# pragotron-master-clock-1_0.net
KiCad netlist of a schematic drawn in EAGLE
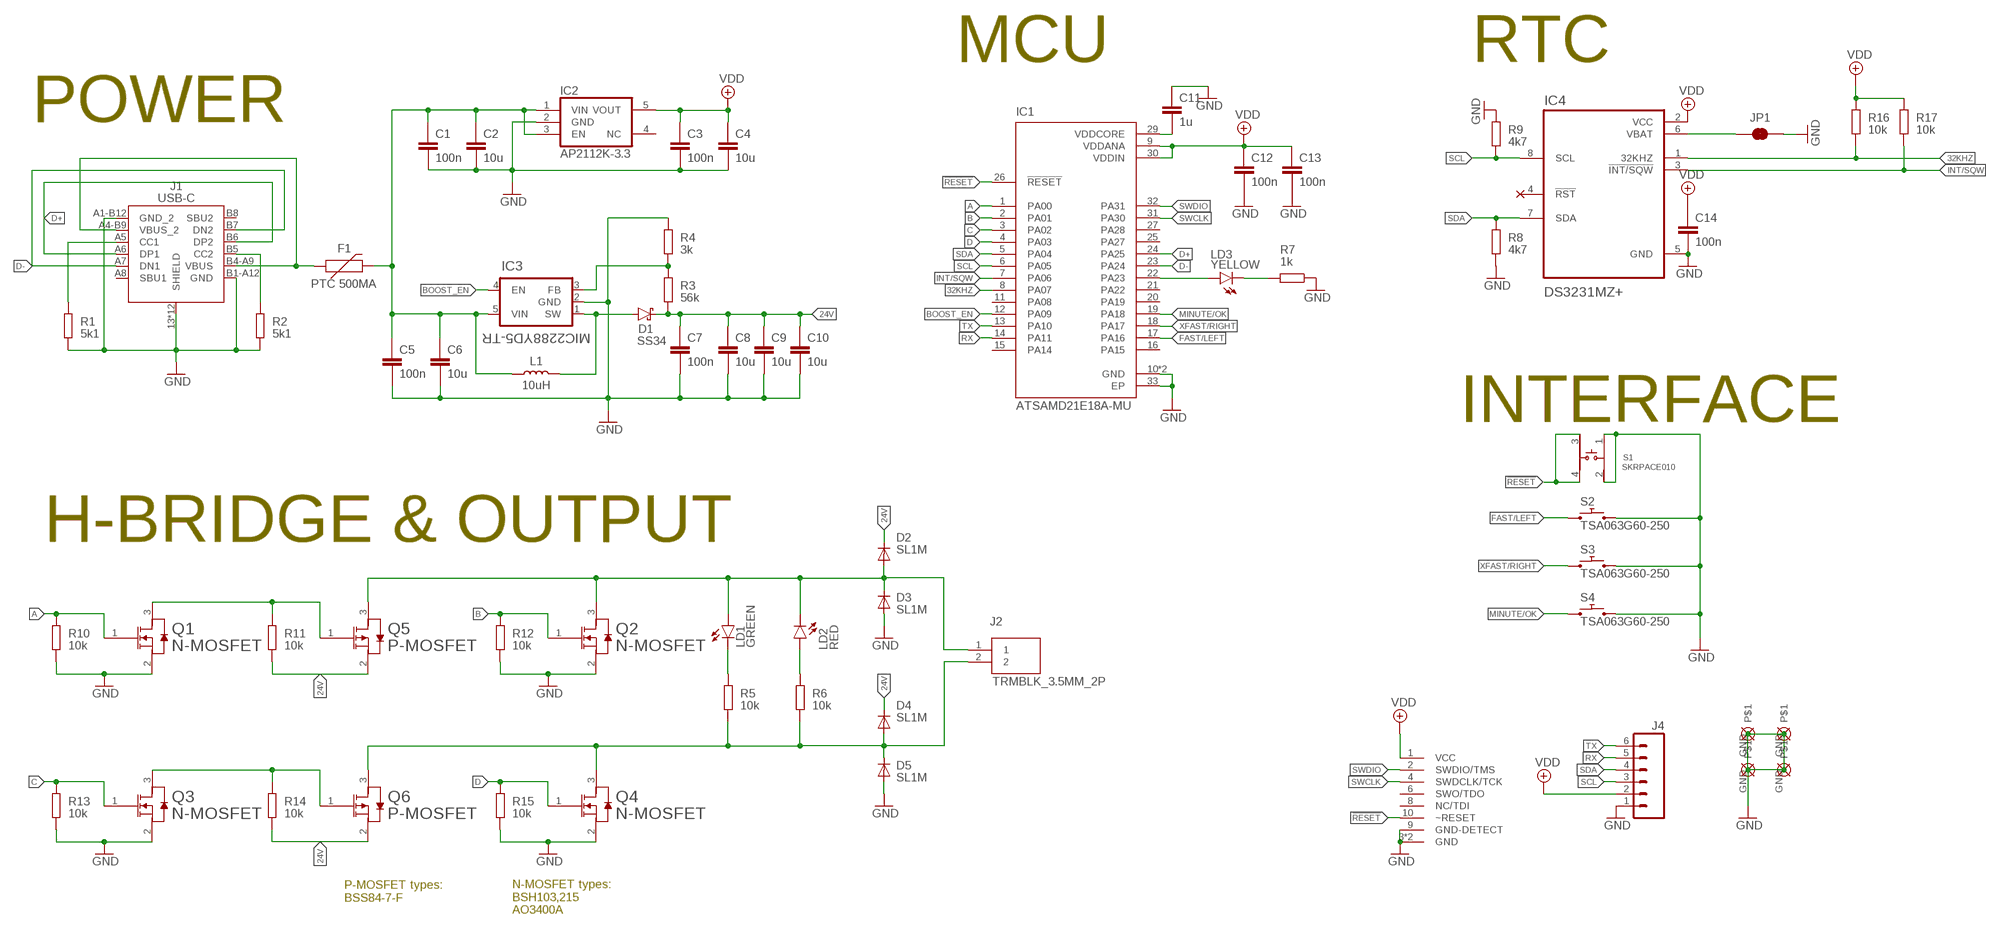
[diagram p0: schematic, sheet 1]

(export (version "E")
  (design (tool "Eeschema 10.0.6"))
  (components
    (comp (ref "C1")
      (value "100n")
      (footprint "eagle-import:CAPACITOR0603")
      (libsource (lib "eagle-import") (part "CAPACITOR0603"))
    )
    (comp (ref "C2")
      (value "10u")
      (footprint "eagle-import:CAPACITOR0805")
      (libsource (lib "eagle-import") (part "CAPACITOR0805"))
    )
    (comp (ref "C3")
      (value "100n")
      (footprint "eagle-import:CAPACITOR0603")
      (libsource (lib "eagle-import") (part "CAPACITOR0603"))
    )
    (comp (ref "C4")
      (value "10u")
      (footprint "eagle-import:CAPACITOR0805")
      (libsource (lib "eagle-import") (part "CAPACITOR0805"))
    )
    (comp (ref "C5")
      (value "100n")
      (footprint "eagle-import:CAPACITOR0603")
      (libsource (lib "eagle-import") (part "CAPACITOR0603"))
    )
    (comp (ref "C6")
      (value "10u")
      (footprint "eagle-import:CAPACITOR0805")
      (libsource (lib "eagle-import") (part "CAPACITOR0805"))
    )
    (comp (ref "C7")
      (value "100n")
      (footprint "eagle-import:CAPACITOR0603")
      (libsource (lib "eagle-import") (part "CAPACITOR0603"))
    )
    (comp (ref "C8")
      (value "10u")
      (footprint "eagle-import:CAPACITOR0805")
      (libsource (lib "eagle-import") (part "CAPACITOR0805"))
    )
    (comp (ref "C9")
      (value "10u")
      (footprint "eagle-import:CAPACITOR0805")
      (libsource (lib "eagle-import") (part "CAPACITOR0805"))
    )
    (comp (ref "C10")
      (value "10u")
      (footprint "eagle-import:CAPACITOR0805")
      (libsource (lib "eagle-import") (part "CAPACITOR0805"))
    )
    (comp (ref "C11")
      (value "1u")
      (footprint "eagle-import:CAPACITOR0603")
      (libsource (lib "eagle-import") (part "CAPACITOR0603"))
    )
    (comp (ref "C12")
      (value "100n")
      (footprint "eagle-import:CAPACITOR0603")
      (libsource (lib "eagle-import") (part "CAPACITOR0603"))
    )
    (comp (ref "C13")
      (value "100n")
      (footprint "eagle-import:CAPACITOR0603")
      (libsource (lib "eagle-import") (part "CAPACITOR0603"))
    )
    (comp (ref "C14")
      (value "100n")
      (footprint "eagle-import:CAPACITOR0603")
      (libsource (lib "eagle-import") (part "CAPACITOR0603"))
    )
    (comp (ref "D1")
      (value "SS34")
      (footprint "eagle-import:SMA")
      (libsource (lib "eagle-import") (part "SS34"))
    )
    (comp (ref "D2")
      (value "SL1M")
      (footprint "eagle-import:SOD123")
      (libsource (lib "eagle-import") (part "SL1M"))
    )
    (comp (ref "D3")
      (value "SL1M")
      (footprint "eagle-import:SOD123")
      (libsource (lib "eagle-import") (part "SL1M"))
    )
    (comp (ref "D4")
      (value "SL1M")
      (footprint "eagle-import:SOD123")
      (libsource (lib "eagle-import") (part "SL1M"))
    )
    (comp (ref "D5")
      (value "SL1M")
      (footprint "eagle-import:SOD123")
      (libsource (lib "eagle-import") (part "SL1M"))
    )
    (comp (ref "F1")
      (value "PTC 500MA")
      (footprint "eagle-import:PTC0805")
      (fields (field (name "MPN") "SR020-09"))
      (libsource (lib "eagle-import") (part "PTC200MA"))
    )
    (comp (ref "H1")
      (value "HOLE_3MM_GND_CORNER")
      (footprint "eagle-import:3MM_HOLE_GND_CORNER")
      (libsource (lib "eagle-import") (part "HOLE_3MM_GND_CORNER"))
    )
    (comp (ref "H2")
      (value "HOLE_3MM_GND_CORNER")
      (footprint "eagle-import:3MM_HOLE_GND_CORNER")
      (libsource (lib "eagle-import") (part "HOLE_3MM_GND_CORNER"))
    )
    (comp (ref "H3")
      (value "HOLE_3MM_GND_CORNER")
      (footprint "eagle-import:3MM_HOLE_GND_CORNER")
      (libsource (lib "eagle-import") (part "HOLE_3MM_GND_CORNER"))
    )
    (comp (ref "H4")
      (value "HOLE_3MM_GND_CORNER")
      (footprint "eagle-import:3MM_HOLE_GND_CORNER")
      (libsource (lib "eagle-import") (part "HOLE_3MM_GND_CORNER"))
    )
    (comp (ref "IC1")
      (value "ATSAMD21E18A-MU")
      (footprint "eagle-import:QFN50P500X500X100-33N")
      (fields (field (name "DIGIKEY_PART_NUMBER") "ATSAMD21E18A-MU-ND") (field (name "MF") "Microchip"))
      (libsource (lib "eagle-import") (part "ATSAMD21E18A-MU"))
    )
    (comp (ref "IC2")
      (value "AP2112K-3.3")
      (footprint "eagle-import:SOT23-5")
      (libsource (lib "eagle-import") (part "AP2205-W5-7"))
    )
    (comp (ref "IC3")
      (value "MIC2288YD5-TR")
      (footprint "eagle-import:SOT23-5")
      (libsource (lib "eagle-import") (part "MIC2288YD5-TR"))
    )
    (comp (ref "IC4")
      (value "DS3231MZ+")
      (footprint "eagle-import:SO8")
      (fields
        (field (name "DIGI-KEY_PART_NUMBER") "DS3231MZ+-ND")
        (field (name "MF") "Maxim Integrated Products")
      )
      (libsource (lib "eagle-import") (part "DS3231MZ+"))
    )
    (comp (ref "J1")
      (value "USB-C")
      (footprint "eagle-import:USB-C")
      (libsource (lib "eagle-import") (part "USB-C"))
    )
    (comp (ref "J2")
      (value "TRMBLK_3.5MM_2P")
      (footprint "eagle-import:TRMBLK_3.5MM_2P")
      (libsource (lib "eagle-import") (part "TRMBLK_3.5MM_2P"))
    )
    (comp (ref "J3")
      (value "2X5_PITCH_1.27MMTH_NOKEY_UNSHROUDED")
      (footprint "eagle-import:CON-CORTEX_2X5_0.05__TH_NS")
      (libsource (lib "eagle-import") (part "2X5_PITCH_1.27MMTH_NOKEY_UNSHROUDED"))
    )
    (comp (ref "J4")
      (value "M06NO_SILK")
      (footprint "eagle-import:1X06_NO_SILK")
      (libsource (lib "eagle-import") (part "M06NO_SILK"))
    )
    (comp (ref "JP1")
      (value "JUMPER-SMT_2_NC_TRACE_NO-SILK")
      (footprint "eagle-import:SMT-JUMPER_2_NC_TRACE_NO-SILK")
      (libsource (lib "eagle-import") (part "JUMPER-SMT_2_NC_TRACE_NO-SILK"))
    )
    (comp (ref "L1")
      (value "10uH")
      (footprint "eagle-import:ETQP3MXXXKVP")
      (fields
        (field (name "DIGI-KEY_PART_NUMBER") "P19755TR-ND")
        (field (name "MF") "Panasonic")
        (field (name "MP") "ETQP3M100KVP")
      )
      (libsource (lib "eagle-import") (part "ETQP3MXXXKVP"))
    )
    (comp (ref "LD1")
      (value "GREEN")
      (footprint "eagle-import:LED_0603")
      (libsource (lib "eagle-import") (part "LED_SMT"))
    )
    (comp (ref "LD2")
      (value "RED")
      (footprint "eagle-import:LED_0603")
      (libsource (lib "eagle-import") (part "LED_SMT"))
    )
    (comp (ref "LD3")
      (value "YELLOW")
      (footprint "eagle-import:LED_0603")
      (libsource (lib "eagle-import") (part "LED_SMT"))
    )
    (comp (ref "Q1")
      (value "N-MOSFET")
      (footprint "eagle-import:SOT23")
      (libsource (lib "eagle-import") (part "N-MOSFET"))
    )
    (comp (ref "Q2")
      (value "N-MOSFET")
      (footprint "eagle-import:SOT23")
      (libsource (lib "eagle-import") (part "N-MOSFET"))
    )
    (comp (ref "Q3")
      (value "N-MOSFET")
      (footprint "eagle-import:SOT23")
      (libsource (lib "eagle-import") (part "N-MOSFET"))
    )
    (comp (ref "Q4")
      (value "N-MOSFET")
      (footprint "eagle-import:SOT23")
      (libsource (lib "eagle-import") (part "N-MOSFET"))
    )
    (comp (ref "Q5")
      (value "P-MOSFET")
      (footprint "eagle-import:SOT23")
      (libsource (lib "eagle-import") (part "P-MOSFET"))
    )
    (comp (ref "Q6")
      (value "P-MOSFET")
      (footprint "eagle-import:SOT23")
      (libsource (lib "eagle-import") (part "P-MOSFET"))
    )
    (comp (ref "R1")
      (value "5k1")
      (footprint "eagle-import:RESISTOR0603")
      (libsource (lib "eagle-import") (part "RESISTOR0603"))
    )
    (comp (ref "R2")
      (value "5k1")
      (footprint "eagle-import:RESISTOR0603")
      (libsource (lib "eagle-import") (part "RESISTOR0603"))
    )
    (comp (ref "R3")
      (value "56k")
      (footprint "eagle-import:RESISTOR0603")
      (libsource (lib "eagle-import") (part "RESISTOR0603"))
    )
    (comp (ref "R4")
      (value "3k")
      (footprint "eagle-import:RESISTOR0603")
      (libsource (lib "eagle-import") (part "RESISTOR0603"))
    )
    (comp (ref "R5")
      (value "10k")
      (footprint "eagle-import:RESISTOR0603")
      (libsource (lib "eagle-import") (part "RESISTOR0603"))
    )
    (comp (ref "R6")
      (value "10k")
      (footprint "eagle-import:RESISTOR0603")
      (libsource (lib "eagle-import") (part "RESISTOR0603"))
    )
    (comp (ref "R7")
      (value "1k")
      (footprint "eagle-import:RESISTOR0603")
      (libsource (lib "eagle-import") (part "RESISTOR0603"))
    )
    (comp (ref "R8")
      (value "4k7")
      (footprint "eagle-import:RESISTOR0603")
      (libsource (lib "eagle-import") (part "RESISTOR0603"))
    )
    (comp (ref "R9")
      (value "4k7")
      (footprint "eagle-import:RESISTOR0603")
      (libsource (lib "eagle-import") (part "RESISTOR0603"))
    )
    (comp (ref "R10")
      (value "10k")
      (footprint "eagle-import:RESISTOR0603")
      (libsource (lib "eagle-import") (part "RESISTOR0603"))
    )
    (comp (ref "R11")
      (value "10k")
      (footprint "eagle-import:RESISTOR0603")
      (libsource (lib "eagle-import") (part "RESISTOR0603"))
    )
    (comp (ref "R12")
      (value "10k")
      (footprint "eagle-import:RESISTOR0603")
      (libsource (lib "eagle-import") (part "RESISTOR0603"))
    )
    (comp (ref "R13")
      (value "10k")
      (footprint "eagle-import:RESISTOR0603")
      (libsource (lib "eagle-import") (part "RESISTOR0603"))
    )
    (comp (ref "R14")
      (value "10k")
      (footprint "eagle-import:RESISTOR0603")
      (libsource (lib "eagle-import") (part "RESISTOR0603"))
    )
    (comp (ref "R15")
      (value "10k")
      (footprint "eagle-import:RESISTOR0603")
      (libsource (lib "eagle-import") (part "RESISTOR0603"))
    )
    (comp (ref "R16")
      (value "10k")
      (footprint "eagle-import:RESISTOR0603")
      (libsource (lib "eagle-import") (part "RESISTOR0603"))
    )
    (comp (ref "R17")
      (value "10k")
      (footprint "eagle-import:RESISTOR0603")
      (libsource (lib "eagle-import") (part "RESISTOR0603"))
    )
    (comp (ref "S1")
      (value "SKRPACE010")
      (footprint "eagle-import:SKRPACE010")
      (fields (field (name "MF") "ALPS"))
      (libsource (lib "eagle-import") (part "SKRPACE010"))
    )
    (comp (ref "S2")
      (value "TSA063G60-250")
      (footprint "eagle-import:TACTILE-SMT-SMALL-PADS")
      (libsource (lib "eagle-import") (part "PUSH_MOMENTARY_SMT_6X6MM_SMALL_PADS"))
    )
    (comp (ref "S3")
      (value "TSA063G60-250")
      (footprint "eagle-import:TACTILE-SMT-SMALL-PADS")
      (libsource (lib "eagle-import") (part "PUSH_MOMENTARY_SMT_6X6MM_SMALL_PADS"))
    )
    (comp (ref "S4")
      (value "TSA063G60-250")
      (footprint "eagle-import:TACTILE-SMT-SMALL-PADS")
      (libsource (lib "eagle-import") (part "PUSH_MOMENTARY_SMT_6X6MM_SMALL_PADS"))
    )
  )
  (nets
    (net (code "1") (name "/~{RESET}") (class "Default")
      (node (ref "IC1") (pin "26") (pinfunction "~{RESET}_26") (pintype "input"))
      (node (ref "J3") (pin "10") (pinfunction "~{RESET}_10") (pintype "bidirectional"))
      (node (ref "S1") (pin "3") (pinfunction "3_3") (pintype "bidirectional"))
      (node (ref "S1") (pin "4") (pinfunction "4_4") (pintype "bidirectional"))
    )
    (net (code "2") (name "24V") (class "Default")
      (node (ref "C10") (pin "1") (pinfunction "1_1") (pintype "passive"))
      (node (ref "C7") (pin "1") (pinfunction "1_1") (pintype "passive"))
      (node (ref "C8") (pin "1") (pinfunction "1_1") (pintype "passive"))
      (node (ref "C9") (pin "1") (pinfunction "1_1") (pintype "passive"))
      (node (ref "D1") (pin "C") (pinfunction "C_C") (pintype "passive"))
      (node (ref "D2") (pin "C") (pinfunction "C_C") (pintype "passive"))
      (node (ref "D4") (pin "C") (pinfunction "C_C") (pintype "passive"))
      (node (ref "Q5") (pin "2") (pinfunction "SOURCE_2") (pintype "passive"))
      (node (ref "Q6") (pin "2") (pinfunction "SOURCE_2") (pintype "passive"))
      (node (ref "R11") (pin "1") (pinfunction "1_1") (pintype "passive"))
      (node (ref "R14") (pin "1") (pinfunction "1_1") (pintype "passive"))
      (node (ref "R3") (pin "1") (pinfunction "1_1") (pintype "passive"))
    )
    (net (code "3") (name "32KHZ") (class "Default")
      (node (ref "IC1") (pin "8") (pinfunction "PA07_8") (pintype "bidirectional"))
      (node (ref "IC4") (pin "1") (pinfunction "32KHZ_1") (pintype "output"))
      (node (ref "R16") (pin "1") (pinfunction "1_1") (pintype "passive"))
    )
    (net (code "4") (name "A") (class "Default")
      (node (ref "IC1") (pin "1") (pinfunction "PA00_1") (pintype "bidirectional"))
      (node (ref "Q1") (pin "1") (pinfunction "GATE_1") (pintype "passive"))
      (node (ref "R10") (pin "2") (pinfunction "2_2") (pintype "passive"))
    )
    (net (code "5") (name "B") (class "Default")
      (node (ref "IC1") (pin "2") (pinfunction "PA01_2") (pintype "bidirectional"))
      (node (ref "Q2") (pin "1") (pinfunction "GATE_1") (pintype "passive"))
      (node (ref "R12") (pin "2") (pinfunction "2_2") (pintype "passive"))
    )
    (net (code "6") (name "BOOST_EN") (class "Default")
      (node (ref "IC1") (pin "12") (pinfunction "PA09_12") (pintype "bidirectional"))
      (node (ref "IC3") (pin "4") (pinfunction "EN_4") (pintype "input"))
    )
    (net (code "7") (name "C") (class "Default")
      (node (ref "IC1") (pin "3") (pinfunction "PA02_3") (pintype "bidirectional"))
      (node (ref "Q3") (pin "1") (pinfunction "GATE_1") (pintype "passive"))
      (node (ref "R13") (pin "2") (pinfunction "2_2") (pintype "passive"))
    )
    (net (code "8") (name "D") (class "Default")
      (node (ref "IC1") (pin "4") (pinfunction "PA03_4") (pintype "bidirectional"))
      (node (ref "Q4") (pin "1") (pinfunction "GATE_1") (pintype "passive"))
      (node (ref "R15") (pin "2") (pinfunction "2_2") (pintype "passive"))
    )
    (net (code "9") (name "D+") (class "Default")
      (node (ref "IC1") (pin "24") (pinfunction "PA25_24") (pintype "bidirectional"))
      (node (ref "J1") (pin "A6") (pinfunction "DP1_A6") (pintype "bidirectional"))
      (node (ref "J1") (pin "B6") (pinfunction "DP2_B6") (pintype "bidirectional"))
    )
    (net (code "10") (name "D-") (class "Default")
      (node (ref "IC1") (pin "23") (pinfunction "PA24_23") (pintype "bidirectional"))
      (node (ref "J1") (pin "A7") (pinfunction "DN1_A7") (pintype "bidirectional"))
      (node (ref "J1") (pin "B7") (pinfunction "DN2_B7") (pintype "bidirectional"))
    )
    (net (code "11") (name "FAST{slash}LEFT") (class "Default")
      (node (ref "IC1") (pin "17") (pinfunction "PA16_17") (pintype "bidirectional"))
      (node (ref "S2") (pin "1") (pinfunction "1_1") (pintype "passive"))
      (node (ref "S2") (pin "2") (pinfunction "1_2") (pintype "passive"))
    )
    (net (code "12") (name "GND") (class "Default")
      (node (ref "C1") (pin "2") (pinfunction "2_2") (pintype "passive"))
      (node (ref "C10") (pin "2") (pinfunction "2_2") (pintype "passive"))
      (node (ref "C11") (pin "1") (pinfunction "1_1") (pintype "passive"))
      (node (ref "C12") (pin "2") (pinfunction "2_2") (pintype "passive"))
      (node (ref "C13") (pin "2") (pinfunction "2_2") (pintype "passive"))
      (node (ref "C14") (pin "2") (pinfunction "2_2") (pintype "passive"))
      (node (ref "C2") (pin "2") (pinfunction "2_2") (pintype "passive"))
      (node (ref "C3") (pin "2") (pinfunction "2_2") (pintype "passive"))
      (node (ref "C4") (pin "2") (pinfunction "2_2") (pintype "passive"))
      (node (ref "C5") (pin "2") (pinfunction "2_2") (pintype "passive"))
      (node (ref "C6") (pin "2") (pinfunction "2_2") (pintype "passive"))
      (node (ref "C7") (pin "2") (pinfunction "2_2") (pintype "passive"))
      (node (ref "C8") (pin "2") (pinfunction "2_2") (pintype "passive"))
      (node (ref "C9") (pin "2") (pinfunction "2_2") (pintype "passive"))
      (node (ref "D3") (pin "A") (pinfunction "A_A") (pintype "passive"))
      (node (ref "D5") (pin "A") (pinfunction "A_A") (pintype "passive"))
      (node (ref "H1") (pin "GND") (pinfunction "P$1_GND") (pintype "bidirectional"))
      (node (ref "H2") (pin "GND") (pinfunction "P$1_GND") (pintype "bidirectional"))
      (node (ref "H3") (pin "GND") (pinfunction "P$1_GND") (pintype "bidirectional"))
      (node (ref "H4") (pin "GND") (pinfunction "P$1_GND") (pintype "bidirectional"))
      (node (ref "IC1") (pin "10") (pinfunction "GND_10") (pintype "power_in"))
      (node (ref "IC1") (pin "28") (pinfunction "GND_28") (pintype "power_in"))
      (node (ref "IC1") (pin "33") (pinfunction "EP_33") (pintype "power_in"))
      (node (ref "IC2") (pin "2") (pinfunction "GND_2") (pintype "power_in"))
      (node (ref "IC3") (pin "2") (pinfunction "GND_2") (pintype "power_in"))
      (node (ref "IC4") (pin "5") (pinfunction "GND_5") (pintype "power_in"))
      (node (ref "J1") (pin "13") (pinfunction "SHIELD_13") (pintype "bidirectional"))
      (node (ref "J1") (pin "14") (pinfunction "SHIELD_14") (pintype "bidirectional"))
      (node (ref "J1") (pin "15") (pinfunction "SHIELD_15") (pintype "bidirectional"))
      (node (ref "J1") (pin "16") (pinfunction "SHIELD_16") (pintype "bidirectional"))
      (node (ref "J1") (pin "A1-B12") (pinfunction "GND_2_A1-B12") (pintype "passive"))
      (node (ref "J1") (pin "B1-A12") (pinfunction "GND_B1-A12") (pintype "passive"))
      (node (ref "J1") (pin "S_1_H1") (pinfunction "SHIELD_S_1_H1") (pintype "bidirectional"))
      (node (ref "J1") (pin "S_1_H2") (pinfunction "SHIELD_S_1_H2") (pintype "bidirectional"))
      (node (ref "J1") (pin "S_2_H1") (pinfunction "SHIELD_S_2_H1") (pintype "bidirectional"))
      (node (ref "J1") (pin "S_2_H2") (pinfunction "SHIELD_S_2_H2") (pintype "bidirectional"))
      (node (ref "J1") (pin "S_3_H1") (pinfunction "SHIELD_S_3_H1") (pintype "bidirectional"))
      (node (ref "J1") (pin "S_3_H2") (pinfunction "SHIELD_S_3_H2") (pintype "bidirectional"))
      (node (ref "J1") (pin "S_4_H1") (pinfunction "SHIELD_S_4_H1") (pintype "bidirectional"))
      (node (ref "J1") (pin "S_4_H2") (pinfunction "SHIELD_S_4_H2") (pintype "bidirectional"))
      (node (ref "J3") (pin "3") (pinfunction "GND_3") (pintype "bidirectional"))
      (node (ref "J3") (pin "5") (pinfunction "GND_5") (pintype "bidirectional"))
      (node (ref "J3") (pin "9") (pinfunction "GND-DETECT_9") (pintype "bidirectional"))
      (node (ref "J4") (pin "1") (pinfunction "1_1") (pintype "passive"))
      (node (ref "JP1") (pin "2") (pinfunction "2_2") (pintype "passive"))
      (node (ref "Q1") (pin "2") (pinfunction "SOURCE_2") (pintype "passive"))
      (node (ref "Q2") (pin "2") (pinfunction "SOURCE_2") (pintype "passive"))
      (node (ref "Q3") (pin "2") (pinfunction "SOURCE_2") (pintype "passive"))
      (node (ref "Q4") (pin "2") (pinfunction "SOURCE_2") (pintype "passive"))
      (node (ref "R1") (pin "1") (pinfunction "1_1") (pintype "passive"))
      (node (ref "R10") (pin "1") (pinfunction "1_1") (pintype "passive"))
      (node (ref "R12") (pin "1") (pinfunction "1_1") (pintype "passive"))
      (node (ref "R13") (pin "1") (pinfunction "1_1") (pintype "passive"))
      (node (ref "R15") (pin "1") (pinfunction "1_1") (pintype "passive"))
      (node (ref "R2") (pin "1") (pinfunction "1_1") (pintype "passive"))
      (node (ref "R4") (pin "2") (pinfunction "2_2") (pintype "passive"))
      (node (ref "R7") (pin "1") (pinfunction "1_1") (pintype "passive"))
      (node (ref "R8") (pin "1") (pinfunction "1_1") (pintype "passive"))
      (node (ref "R9") (pin "2") (pinfunction "2_2") (pintype "passive"))
      (node (ref "S1") (pin "1") (pinfunction "1_1") (pintype "bidirectional"))
      (node (ref "S1") (pin "2") (pinfunction "2_2") (pintype "bidirectional"))
      (node (ref "S2") (pin "3") (pinfunction "2_3") (pintype "passive"))
      (node (ref "S2") (pin "4") (pinfunction "2_4") (pintype "passive"))
      (node (ref "S3") (pin "3") (pinfunction "2_3") (pintype "passive"))
      (node (ref "S3") (pin "4") (pinfunction "2_4") (pintype "passive"))
      (node (ref "S4") (pin "3") (pinfunction "2_3") (pintype "passive"))
      (node (ref "S4") (pin "4") (pinfunction "2_4") (pintype "passive"))
    )
    (net (code "13") (name "INT{slash}SQW") (class "Default")
      (node (ref "IC1") (pin "7") (pinfunction "PA06_7") (pintype "bidirectional"))
      (node (ref "IC4") (pin "3") (pinfunction "~{INT/SQW}_3") (pintype "output"))
      (node (ref "R17") (pin "1") (pinfunction "1_1") (pintype "passive"))
    )
    (net (code "14") (name "MINUTE{slash}OK") (class "Default")
      (node (ref "IC1") (pin "19") (pinfunction "PA18_19") (pintype "bidirectional"))
      (node (ref "S4") (pin "1") (pinfunction "1_1") (pintype "passive"))
      (node (ref "S4") (pin "2") (pinfunction "1_2") (pintype "passive"))
    )
    (net (code "15") (name "Net-(F1-1)") (class "Default")
      (node (ref "F1") (pin "2") (pinfunction "1_2") (pintype "bidirectional"))
      (node (ref "J1") (pin "A4-B9") (pinfunction "VBUS_2_A4-B9") (pintype "power_in"))
      (node (ref "J1") (pin "B4-A9") (pinfunction "VBUS_B4-A9") (pintype "power_in"))
    )
    (net (code "16") (name "Net-(F1-2)") (class "Default")
      (node (ref "C1") (pin "1") (pinfunction "1_1") (pintype "passive"))
      (node (ref "C2") (pin "1") (pinfunction "1_1") (pintype "passive"))
      (node (ref "C5") (pin "1") (pinfunction "1_1") (pintype "passive"))
      (node (ref "C6") (pin "1") (pinfunction "1_1") (pintype "passive"))
      (node (ref "F1") (pin "3") (pinfunction "2_3") (pintype "bidirectional"))
      (node (ref "IC2") (pin "1") (pinfunction "VIN_1") (pintype "power_in"))
      (node (ref "IC2") (pin "3") (pinfunction "EN_3") (pintype "input"))
      (node (ref "IC3") (pin "5") (pinfunction "VIN_5") (pintype "input"))
      (node (ref "L1") (pin "1") (pinfunction "1_1") (pintype "passive"))
    )
    (net (code "17") (name "Net-(IC1-PA23)") (class "Default")
      (node (ref "IC1") (pin "22") (pinfunction "PA23_22") (pintype "bidirectional"))
      (node (ref "LD3") (pin "A") (pinfunction "A_A") (pintype "passive"))
    )
    (net (code "18") (name "Net-(IC1-VDDCORE)") (class "Default")
      (node (ref "C11") (pin "2") (pinfunction "2_2") (pintype "passive"))
      (node (ref "IC1") (pin "29") (pinfunction "VDDCORE_29") (pintype "power_in"))
    )
    (net (code "19") (name "Net-(IC3-FB)") (class "Default")
      (node (ref "IC3") (pin "3") (pinfunction "FB_3") (pintype "input"))
      (node (ref "R3") (pin "2") (pinfunction "2_2") (pintype "passive"))
      (node (ref "R4") (pin "1") (pinfunction "1_1") (pintype "passive"))
    )
    (net (code "20") (name "Net-(IC3-SW)") (class "Default")
      (node (ref "D1") (pin "A") (pinfunction "A_A") (pintype "passive"))
      (node (ref "IC3") (pin "1") (pinfunction "SW_1") (pintype "output"))
      (node (ref "L1") (pin "2") (pinfunction "2_2") (pintype "passive"))
    )
    (net (code "21") (name "Net-(IC4-VBAT)") (class "Default")
      (node (ref "IC4") (pin "6") (pinfunction "VBAT_6") (pintype "power_in"))
      (node (ref "JP1") (pin "1") (pinfunction "1_1") (pintype "passive"))
    )
    (net (code "22") (name "Net-(J1-CC1)") (class "Default")
      (node (ref "J1") (pin "A5") (pinfunction "CC1_A5") (pintype "bidirectional"))
      (node (ref "R1") (pin "2") (pinfunction "2_2") (pintype "passive"))
    )
    (net (code "23") (name "Net-(J1-CC2)") (class "Default")
      (node (ref "J1") (pin "B5") (pinfunction "CC2_B5") (pintype "bidirectional"))
      (node (ref "R2") (pin "2") (pinfunction "2_2") (pintype "passive"))
    )
    (net (code "24") (name "Net-(LD1-C)") (class "Default")
      (node (ref "LD1") (pin "K") (pinfunction "C_K") (pintype "passive"))
      (node (ref "R5") (pin "2") (pinfunction "2_2") (pintype "passive"))
    )
    (net (code "25") (name "Net-(LD2-C)") (class "Default")
      (node (ref "D2") (pin "A") (pinfunction "A_A") (pintype "passive"))
      (node (ref "D3") (pin "C") (pinfunction "C_C") (pintype "passive"))
      (node (ref "J2") (pin "1") (pinfunction "1_1") (pintype "passive"))
      (node (ref "LD1") (pin "A") (pinfunction "A_A") (pintype "passive"))
      (node (ref "LD2") (pin "K") (pinfunction "C_K") (pintype "passive"))
      (node (ref "Q2") (pin "3") (pinfunction "DRAIN_3") (pintype "passive"))
      (node (ref "Q5") (pin "3") (pinfunction "DRAIN_3") (pintype "passive"))
    )
    (net (code "26") (name "Net-(LD2-PadA)") (class "Default")
      (node (ref "LD2") (pin "A") (pinfunction "A_A") (pintype "passive"))
      (node (ref "R6") (pin "2") (pinfunction "2_2") (pintype "passive"))
    )
    (net (code "27") (name "Net-(LD3-C)") (class "Default")
      (node (ref "LD3") (pin "K") (pinfunction "C_K") (pintype "passive"))
      (node (ref "R7") (pin "2") (pinfunction "2_2") (pintype "passive"))
    )
    (net (code "28") (name "Net-(Q1-DRAIN)") (class "Default")
      (node (ref "Q1") (pin "3") (pinfunction "DRAIN_3") (pintype "passive"))
      (node (ref "Q5") (pin "1") (pinfunction "GATE_1") (pintype "passive"))
      (node (ref "R11") (pin "2") (pinfunction "2_2") (pintype "passive"))
    )
    (net (code "29") (name "Net-(Q3-DRAIN)") (class "Default")
      (node (ref "Q3") (pin "3") (pinfunction "DRAIN_3") (pintype "passive"))
      (node (ref "Q6") (pin "1") (pinfunction "GATE_1") (pintype "passive"))
      (node (ref "R14") (pin "2") (pinfunction "2_2") (pintype "passive"))
    )
    (net (code "30") (name "Net-(Q4-DRAIN)") (class "Default")
      (node (ref "D4") (pin "A") (pinfunction "A_A") (pintype "passive"))
      (node (ref "D5") (pin "C") (pinfunction "C_C") (pintype "passive"))
      (node (ref "J2") (pin "2") (pinfunction "2_2") (pintype "passive"))
      (node (ref "Q4") (pin "3") (pinfunction "DRAIN_3") (pintype "passive"))
      (node (ref "Q6") (pin "3") (pinfunction "DRAIN_3") (pintype "passive"))
      (node (ref "R5") (pin "1") (pinfunction "1_1") (pintype "passive"))
      (node (ref "R6") (pin "1") (pinfunction "1_1") (pintype "passive"))
    )
    (net (code "31") (name "RX") (class "Default")
      (node (ref "IC1") (pin "14") (pinfunction "PA11_14") (pintype "bidirectional"))
      (node (ref "J4") (pin "5") (pinfunction "5_5") (pintype "passive"))
    )
    (net (code "32") (name "SCL") (class "Default")
      (node (ref "IC1") (pin "6") (pinfunction "PA05_6") (pintype "bidirectional"))
      (node (ref "IC4") (pin "8") (pinfunction "SCL_8") (pintype "input"))
      (node (ref "J4") (pin "3") (pinfunction "3_3") (pintype "passive"))
      (node (ref "R9") (pin "1") (pinfunction "1_1") (pintype "passive"))
    )
    (net (code "33") (name "SDA") (class "Default")
      (node (ref "IC1") (pin "5") (pinfunction "PA04_5") (pintype "bidirectional"))
      (node (ref "IC4") (pin "7") (pinfunction "SDA_7") (pintype "bidirectional"))
      (node (ref "J4") (pin "4") (pinfunction "4_4") (pintype "passive"))
      (node (ref "R8") (pin "2") (pinfunction "2_2") (pintype "passive"))
    )
    (net (code "34") (name "SWCLK") (class "Default")
      (node (ref "IC1") (pin "31") (pinfunction "PA30_31") (pintype "bidirectional"))
      (node (ref "J3") (pin "4") (pinfunction "SWDCLK/TCK_4") (pintype "bidirectional"))
    )
    (net (code "35") (name "SWDIO") (class "Default")
      (node (ref "IC1") (pin "32") (pinfunction "PA31_32") (pintype "bidirectional"))
      (node (ref "J3") (pin "2") (pinfunction "SWDIO/TMS_2") (pintype "bidirectional"))
    )
    (net (code "36") (name "TX") (class "Default")
      (node (ref "IC1") (pin "13") (pinfunction "PA10_13") (pintype "bidirectional"))
      (node (ref "J4") (pin "6") (pinfunction "6_6") (pintype "passive"))
    )
    (net (code "37") (name "VDD") (class "Default")
      (node (ref "C12") (pin "1") (pinfunction "1_1") (pintype "passive"))
      (node (ref "C13") (pin "1") (pinfunction "1_1") (pintype "passive"))
      (node (ref "C14") (pin "1") (pinfunction "1_1") (pintype "passive"))
      (node (ref "C3") (pin "1") (pinfunction "1_1") (pintype "passive"))
      (node (ref "C4") (pin "1") (pinfunction "1_1") (pintype "passive"))
      (node (ref "IC1") (pin "30") (pinfunction "VDDIN_30") (pintype "power_in"))
      (node (ref "IC1") (pin "9") (pinfunction "VDDANA_9") (pintype "power_in"))
      (node (ref "IC2") (pin "5") (pinfunction "VOUT_5") (pintype "power_in"))
      (node (ref "IC4") (pin "2") (pinfunction "VCC_2") (pintype "power_in"))
      (node (ref "J3") (pin "1") (pinfunction "VCC_1") (pintype "bidirectional"))
      (node (ref "J4") (pin "2") (pinfunction "2_2") (pintype "passive"))
      (node (ref "R16") (pin "2") (pinfunction "2_2") (pintype "passive"))
      (node (ref "R17") (pin "2") (pinfunction "2_2") (pintype "passive"))
    )
    (net (code "38") (name "XFAST{slash}RIGHT") (class "Default")
      (node (ref "IC1") (pin "18") (pinfunction "PA17_18") (pintype "bidirectional"))
      (node (ref "S3") (pin "1") (pinfunction "1_1") (pintype "passive"))
      (node (ref "S3") (pin "2") (pinfunction "1_2") (pintype "passive"))
    )
    (net (code "39") (name "unconnected-(IC1-PA08-Pad11)") (class "Default")
      (node (ref "IC1") (pin "11") (pinfunction "PA08_11") (pintype "bidirectional"))
    )
    (net (code "40") (name "unconnected-(IC1-PA14-Pad15)") (class "Default")
      (node (ref "IC1") (pin "15") (pinfunction "PA14_15") (pintype "bidirectional"))
    )
    (net (code "41") (name "unconnected-(IC1-PA15-Pad16)") (class "Default")
      (node (ref "IC1") (pin "16") (pinfunction "PA15_16") (pintype "bidirectional"))
    )
    (net (code "42") (name "unconnected-(IC1-PA19-Pad20)") (class "Default")
      (node (ref "IC1") (pin "20") (pinfunction "PA19_20") (pintype "bidirectional"))
    )
    (net (code "43") (name "unconnected-(IC1-PA22-Pad21)") (class "Default")
      (node (ref "IC1") (pin "21") (pinfunction "PA22_21") (pintype "bidirectional"))
    )
    (net (code "44") (name "unconnected-(IC1-PA27-Pad25)") (class "Default")
      (node (ref "IC1") (pin "25") (pinfunction "PA27_25") (pintype "bidirectional"))
    )
    (net (code "45") (name "unconnected-(IC1-PA28-Pad27)") (class "Default")
      (node (ref "IC1") (pin "27") (pinfunction "PA28_27") (pintype "bidirectional"))
    )
    (net (code "46") (name "unconnected-(IC2-NC-Pad4)") (class "Default")
      (node (ref "IC2") (pin "4") (pinfunction "NC_4") (pintype "bidirectional"))
    )
    (net (code "47") (name "unconnected-(IC4-~{RST}-Pad4)") (class "Default")
      (node (ref "IC4") (pin "4") (pinfunction "~{RST}_4") (pintype "bidirectional"))
    )
    (net (code "48") (name "unconnected-(J1-SBU1-PadA8)") (class "Default")
      (node (ref "J1") (pin "A8") (pinfunction "SBU1_A8") (pintype "bidirectional"))
    )
    (net (code "49") (name "unconnected-(J1-SBU2-PadB8)") (class "Default")
      (node (ref "J1") (pin "B8") (pinfunction "SBU2_B8") (pintype "bidirectional"))
    )
    (net (code "50") (name "unconnected-(J3-NC{slash}TDI-Pad8)") (class "Default")
      (node (ref "J3") (pin "8") (pinfunction "NC/TDI_8") (pintype "bidirectional"))
    )
    (net (code "51") (name "unconnected-(J3-SWO{slash}TDO-Pad6)") (class "Default")
      (node (ref "J3") (pin "6") (pinfunction "SWO/TDO_6") (pintype "bidirectional"))
    )
  )
)
